# MCU_peripheral.net
KiCad netlist of a schematic drawn in Altium Designer
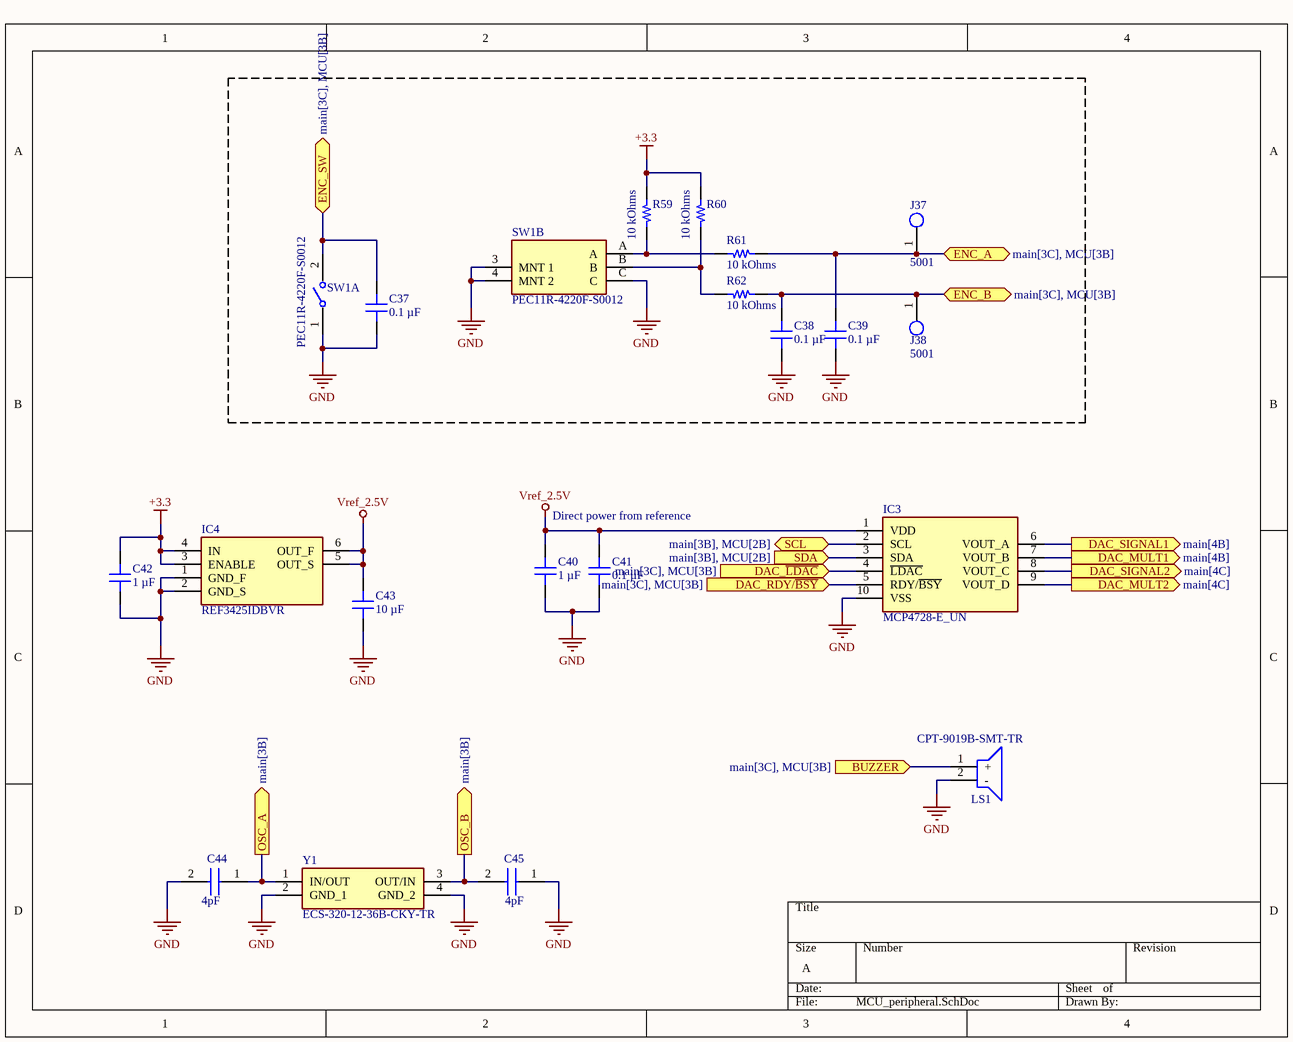
[diagram p0: MCU_peripheral.SchDoc]

(export (version "E")
  (design (tool "Eeschema 10.0.6"))
  (components
    (comp (ref "C37")
      (value "0.1 µF")
      (footprint "CAP 1206_3216 - 0.8MM")
      (description "CAP CER 0.1UF 50V X7R 1206")
      (fields
        (field (name "PART NUMBER") "885012208087")
        (field (name "CAPACITANCE") "0.1 µF")
        (field (name "MANUFACTURER") "Würth Elektronik")
      )
      (libsource (lib "Celestial Altium Library - altium_library") (part "Capacitor"))
    )
    (comp (ref "C38")
      (value "0.1 µF")
      (footprint "CAP 1206_3216 - 0.8MM")
      (description "CAP CER 0.1UF 50V X7R 1206")
      (fields
        (field (name "PART NUMBER") "885012208087")
        (field (name "CAPACITANCE") "0.1 µF")
        (field (name "MANUFACTURER") "Würth Elektronik")
      )
      (libsource (lib "Celestial Altium Library - altium_library") (part "Capacitor"))
    )
    (comp (ref "C39")
      (value "0.1 µF")
      (footprint "CAP 1206_3216 - 0.8MM")
      (description "CAP CER 0.1UF 50V X7R 1206")
      (fields
        (field (name "PART NUMBER") "885012208087")
        (field (name "CAPACITANCE") "0.1 µF")
        (field (name "MANUFACTURER") "Würth Elektronik")
      )
      (libsource (lib "Celestial Altium Library - altium_library") (part "Capacitor"))
    )
    (comp (ref "C40")
      (value "1 µF")
      (footprint "CAP 1206_3216 - 0.8MM")
      (description "CAP CER 1UF 50V X7R 1206")
      (fields
        (field (name "PART NUMBER") "885012208093")
        (field (name "CAPACITANCE") "1 µF")
        (field (name "MANUFACTURER") "Würth Elektronik")
      )
      (libsource (lib "Celestial Altium Library - altium_library") (part "Capacitor"))
    )
    (comp (ref "C41")
      (value "0.1 µF")
      (footprint "CAP 1206_3216 - 0.8MM")
      (description "CAP CER 0.1UF 50V X7R 1206")
      (fields
        (field (name "PART NUMBER") "885012208087")
        (field (name "CAPACITANCE") "0.1 µF")
        (field (name "MANUFACTURER") "Würth Elektronik")
      )
      (libsource (lib "Celestial Altium Library - altium_library") (part "Capacitor"))
    )
    (comp (ref "C42")
      (value "1 µF")
      (footprint "CAP 1206_3216 - 0.8MM")
      (description "CAP CER 1UF 50V X7R 1206")
      (fields
        (field (name "PART NUMBER") "885012208093")
        (field (name "CAPACITANCE") "1 µF")
        (field (name "MANUFACTURER") "Würth Elektronik")
      )
      (libsource (lib "Celestial Altium Library - altium_library") (part "Capacitor"))
    )
    (comp (ref "C43")
      (value "10 µF")
      (footprint "CAP 1206_3216 - 0.8MM")
      (description "CAP CER 10UF 25V X7R 1206")
      (fields
        (field (name "PART NUMBER") "885012208069")
        (field (name "CAPACITANCE") "10 µF")
        (field (name "MANUFACTURER") "Würth Elektronik")
      )
      (libsource (lib "Celestial Altium Library - altium_library") (part "Capacitor"))
    )
    (comp (ref "C44")
      (value "4pF")
      (footprint "CAPC1608X80N")
      (description "Capacitor")
      (fields (field (name "MANUFACTURER_PART_NUMBER") "C1608C0G1H040C080AA"))
      (libsource (lib "za_koncar") (part "C1608C0G1H040C080AA"))
    )
    (comp (ref "C45")
      (value "4pF")
      (footprint "CAPC1608X80N")
      (description "Capacitor")
      (fields (field (name "MANUFACTURER_PART_NUMBER") "C1608C0G1H040C080AA"))
      (libsource (lib "za_koncar") (part "C1608C0G1H040C080AA"))
    )
    (comp (ref "IC3")
      (value "MCP4728-E_UN")
      (footprint "SOP50P490X110-10N")
      (description "Integrated Circuit")
      (fields
        (field (name "MANUFACTURER_PART_NUMBER") "MCP4728-E/UN")
        (field (name "MOUSER PART NUMBER") "579-MCP4728-E/UN")
      )
      (libsource (lib "za_koncar") (part "MCP4728-E_UN"))
    )
    (comp (ref "IC4")
      (value "REF3425IDBVR")
      (footprint "SOT95P280X145-6N")
      (description "Integrated Circuit")
      (fields (field (name "MOUSER PART NUMBER") "595-REF3425IDBVR"))
      (libsource (lib "za_koncar") (part "REF3425IDBVR"))
    )
    (comp (ref "J37")
      (value "5001")
      (footprint "FP-5001-MFG")
      (description "PC TEST POINT MINIATURE BLACK")
      (libsource (lib "za_koncar") (part "CMP-2000-05181-2"))
    )
    (comp (ref "J38")
      (value "5001")
      (footprint "FP-5001-MFG")
      (description "PC TEST POINT MINIATURE BLACK")
      (libsource (lib "za_koncar") (part "CMP-2000-05181-2"))
    )
    (comp (ref "LS1")
      (value "CPT-9019B-SMT-TR")
      (footprint "CPT9019BSMTTR")
      (description "Loudspeaker or Buzzer")
      (fields (field (name "MOUSER PART NUMBER") "179-CPT-9019B-SMT-TR"))
      (libsource (lib "za_koncar") (part "CPT-9019B-SMT-TR"))
    )
    (comp (ref "R59")
      (value "10 kOhms")
      (footprint "YAGEO RES 1206_3216")
      (description "RES SMD 10K OHM 1% 1/4W 1206")
      (fields (field (name "PART NUMBER") "RT1206FRE0710KL") (field (name "MANUFACTURER") "Yageo"))
      (libsource (lib "Celestial Altium Library - altium_library") (part "Resistor"))
    )
    (comp (ref "R60")
      (value "10 kOhms")
      (footprint "YAGEO RES 1206_3216")
      (description "RES SMD 10K OHM 1% 1/4W 1206")
      (fields (field (name "PART NUMBER") "RT1206FRE0710KL") (field (name "MANUFACTURER") "Yageo"))
      (libsource (lib "Celestial Altium Library - altium_library") (part "Resistor"))
    )
    (comp (ref "R61")
      (value "10 kOhms")
      (footprint "YAGEO RES 1206_3216")
      (description "RES SMD 10K OHM 1% 1/4W 1206")
      (fields (field (name "PART NUMBER") "RT1206FRE0710KL") (field (name "MANUFACTURER") "Yageo"))
      (libsource (lib "Celestial Altium Library - altium_library") (part "Resistor"))
    )
    (comp (ref "R62")
      (value "10 kOhms")
      (footprint "YAGEO RES 1206_3216")
      (description "RES SMD 10K OHM 1% 1/4W 1206")
      (fields (field (name "PART NUMBER") "RT1206FRE0710KL") (field (name "MANUFACTURER") "Yageo"))
      (libsource (lib "Celestial Altium Library - altium_library") (part "Resistor"))
    )
    (comp (ref "SW1")
      (value "PEC11R-4220F-S0012")
      (footprint "FP-PEC11R-4220F-S0012-MFG")
      (description "ROTARY ENCODER MECHANICAL 12PPR")
      (libsource (lib "za_koncar") (part "PEC11R-4220F-S0012"))
    )
    (comp (ref "Y1")
      (value "ECS-320-12-36B-CKY-TR")
      (footprint "ECS240836QAESTR")
      (description "Crystal or Oscillator")
      (fields (field (name "MOUSER PART NUMBER") "520-320-12-36B-CKYT"))
      (libsource (lib "za_koncar") (part "ECS-320-12-36B-CKY-TR"))
    )
  )
  (nets
    (net (code "1") (name "+3.3") (class "Default")
      (node (ref "C42") (pin "2") (pinfunction "2_2") (pintype "passive"))
      (node (ref "IC4") (pin "3") (pinfunction "ENABLE_3") (pintype "passive"))
      (node (ref "IC4") (pin "4") (pinfunction "IN_4") (pintype "passive"))
      (node (ref "R59") (pin "1") (pinfunction "1_1") (pintype "passive"))
      (node (ref "R60") (pin "1") (pinfunction "1_1") (pintype "passive"))
    )
    (net (code "2") (name "/BUZZER") (class "Default")
      (node (ref "LS1") (pin "1") (pinfunction "+_1") (pintype "passive"))
    )
    (net (code "3") (name "/DAC_MULT1") (class "Default")
      (node (ref "IC3") (pin "7") (pinfunction "VOUT_B_7") (pintype "passive"))
    )
    (net (code "4") (name "/DAC_MULT2") (class "Default")
      (node (ref "IC3") (pin "9") (pinfunction "VOUT_D_9") (pintype "passive"))
    )
    (net (code "5") (name "/DAC_RDY{slash}~{BSY}") (class "Default")
      (node (ref "IC3") (pin "5") (pinfunction "RDY/~{BSY}_5") (pintype "passive"))
    )
    (net (code "6") (name "/DAC_SIGNAL1") (class "Default")
      (node (ref "IC3") (pin "6") (pinfunction "VOUT_A_6") (pintype "passive"))
    )
    (net (code "7") (name "/DAC_SIGNAL2") (class "Default")
      (node (ref "IC3") (pin "8") (pinfunction "VOUT_C_8") (pintype "passive"))
    )
    (net (code "8") (name "/DAC_~{LDAC}") (class "Default")
      (node (ref "IC3") (pin "4") (pinfunction "~{LDAC}_4") (pintype "passive"))
    )
    (net (code "9") (name "/ENC_A") (class "Default")
      (node (ref "C39") (pin "2") (pinfunction "2_2") (pintype "passive"))
      (node (ref "J37") (pin "1") (pinfunction "1_1") (pintype "passive"))
      (node (ref "R61") (pin "2") (pinfunction "2_2") (pintype "passive"))
    )
    (net (code "10") (name "/ENC_B") (class "Default")
      (node (ref "C38") (pin "2") (pinfunction "2_2") (pintype "passive"))
      (node (ref "J38") (pin "1") (pinfunction "1_1") (pintype "passive"))
      (node (ref "R62") (pin "2") (pinfunction "2_2") (pintype "passive"))
    )
    (net (code "11") (name "/ENC_SW") (class "Default")
      (node (ref "C37") (pin "2") (pinfunction "2_2") (pintype "passive"))
      (node (ref "SW1") (pin "2") (pinfunction "2_2") (pintype "passive"))
    )
    (net (code "12") (name "/OSC_A") (class "Default")
      (node (ref "C44") (pin "1") (pinfunction "1_1") (pintype "passive"))
      (node (ref "Y1") (pin "1") (pinfunction "IN/OUT_1") (pintype "passive"))
    )
    (net (code "13") (name "/OSC_B") (class "Default")
      (node (ref "C45") (pin "2") (pinfunction "2_2") (pintype "passive"))
      (node (ref "Y1") (pin "3") (pinfunction "OUT/IN_3") (pintype "passive"))
    )
    (net (code "14") (name "/SCL") (class "Default")
      (node (ref "IC3") (pin "2") (pinfunction "SCL_2") (pintype "passive"))
    )
    (net (code "15") (name "/SDA") (class "Default")
      (node (ref "IC3") (pin "3") (pinfunction "SDA_3") (pintype "passive"))
    )
    (net (code "16") (name "GND") (class "Default")
      (node (ref "C37") (pin "1") (pinfunction "1_1") (pintype "passive"))
      (node (ref "C38") (pin "1") (pinfunction "1_1") (pintype "passive"))
      (node (ref "C39") (pin "1") (pinfunction "1_1") (pintype "passive"))
      (node (ref "C40") (pin "1") (pinfunction "1_1") (pintype "passive"))
      (node (ref "C41") (pin "1") (pinfunction "1_1") (pintype "passive"))
      (node (ref "C42") (pin "1") (pinfunction "1_1") (pintype "passive"))
      (node (ref "C43") (pin "1") (pinfunction "1_1") (pintype "passive"))
      (node (ref "C44") (pin "2") (pinfunction "2_2") (pintype "passive"))
      (node (ref "C45") (pin "1") (pinfunction "1_1") (pintype "passive"))
      (node (ref "IC3") (pin "10") (pinfunction "VSS_10") (pintype "passive"))
      (node (ref "IC4") (pin "1") (pinfunction "GND_F_1") (pintype "passive"))
      (node (ref "IC4") (pin "2") (pinfunction "GND_S_2") (pintype "passive"))
      (node (ref "LS1") (pin "2") (pinfunction "-_2") (pintype "passive"))
      (node (ref "SW1") (pin "1") (pinfunction "1_1") (pintype "passive"))
      (node (ref "SW1") (pin "3") (pinfunction "MNT_1_3") (pintype "passive"))
      (node (ref "SW1") (pin "4") (pinfunction "MNT_2_4") (pintype "passive"))
      (node (ref "SW1") (pin "C") (pinfunction "C_C") (pintype "passive"))
      (node (ref "Y1") (pin "2") (pinfunction "GND_1_2") (pintype "passive"))
      (node (ref "Y1") (pin "4") (pinfunction "GND_2_4") (pintype "passive"))
    )
    (net (code "17") (name "Net-(R59-Pad2)") (class "Default")
      (node (ref "R59") (pin "2") (pinfunction "2_2") (pintype "passive"))
      (node (ref "R61") (pin "1") (pinfunction "1_1") (pintype "passive"))
      (node (ref "SW1") (pin "A") (pinfunction "A_A") (pintype "passive"))
    )
    (net (code "18") (name "Net-(R60-Pad2)") (class "Default")
      (node (ref "R60") (pin "2") (pinfunction "2_2") (pintype "passive"))
      (node (ref "R62") (pin "1") (pinfunction "1_1") (pintype "passive"))
      (node (ref "SW1") (pin "B") (pinfunction "B_B") (pintype "passive"))
    )
    (net (code "19") (name "Vref_2.5V") (class "Default")
      (node (ref "C40") (pin "2") (pinfunction "2_2") (pintype "passive"))
      (node (ref "C41") (pin "2") (pinfunction "2_2") (pintype "passive"))
      (node (ref "C43") (pin "2") (pinfunction "2_2") (pintype "passive"))
      (node (ref "IC3") (pin "1") (pinfunction "VDD_1") (pintype "passive"))
      (node (ref "IC4") (pin "5") (pinfunction "OUT_S_5") (pintype "passive"))
      (node (ref "IC4") (pin "6") (pinfunction "OUT_F_6") (pintype "passive"))
    )
  )
)
